# Phase.net
KiCad netlist of a schematic drawn in Altium Designer
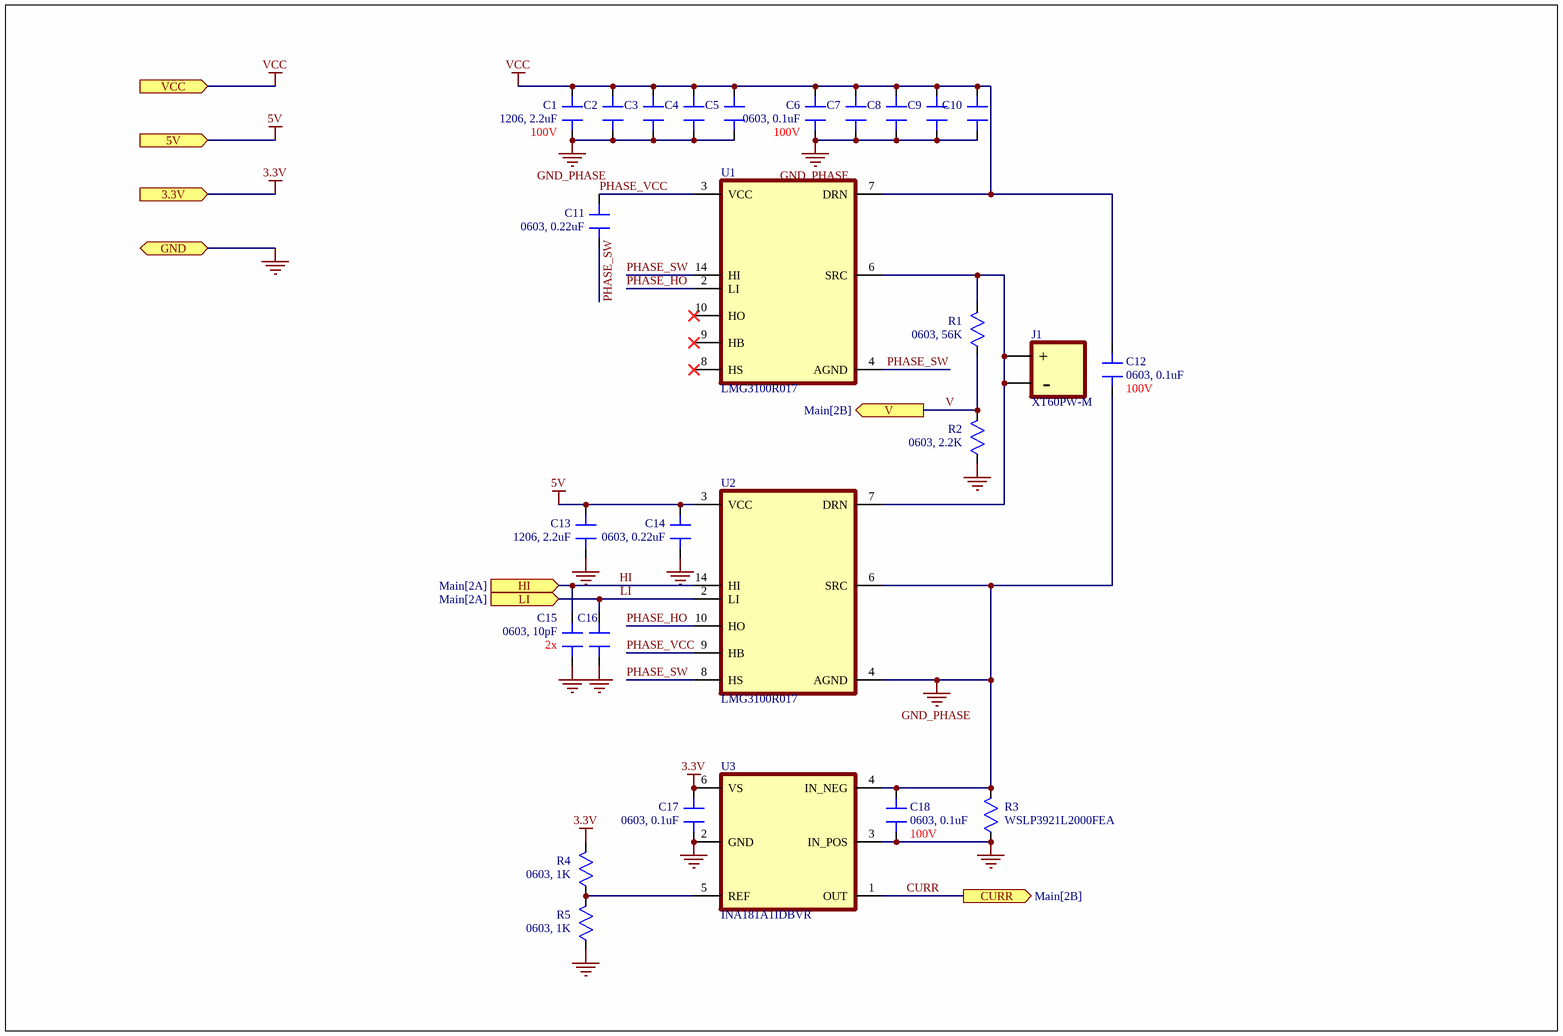
[diagram p0: Phase.SchDoc]

(export (version "E")
  (design (tool "Eeschema 10.0.6"))
  (components
    (comp (ref "C1")
      (value "1206, 2.2uF")
      (footprint "CAP 1206_3216")
      (fields (field (name "VOLTAGE RATING") "100V"))
      (libsource (lib "Passives") (part "1206 Kapasitör"))
    )
    (comp (ref "C2")
      (value "1206, 2.2uF")
      (footprint "CAP 1206_3216")
      (libsource (lib "Passives") (part "1206 Kapasitör"))
    )
    (comp (ref "C3")
      (value "1206, 2.2uF")
      (footprint "CAP 1206_3216")
      (libsource (lib "Passives") (part "1206 Kapasitör"))
    )
    (comp (ref "C4")
      (value "1206, 2.2uF")
      (footprint "CAP 1206_3216")
      (libsource (lib "Passives") (part "1206 Kapasitör"))
    )
    (comp (ref "C5")
      (value "1206, 2.2uF")
      (footprint "CAP 1206_3216")
      (libsource (lib "Passives") (part "1206 Kapasitör"))
    )
    (comp (ref "C6")
      (value "0603, 0.1uF")
      (footprint "CAP 0603_1608")
      (fields (field (name "VOLTAGE RATING") "100V"))
      (libsource (lib "Passives") (part "0603 Kapasitör"))
    )
    (comp (ref "C7")
      (value "0603, 0.1uF")
      (footprint "CAP 0603_1608")
      (libsource (lib "Passives") (part "0603 Kapasitör"))
    )
    (comp (ref "C8")
      (value "0603, 0.1uF")
      (footprint "CAP 0603_1608")
      (libsource (lib "Passives") (part "0603 Kapasitör"))
    )
    (comp (ref "C9")
      (value "0603, 0.1uF")
      (footprint "CAP 0603_1608")
      (libsource (lib "Passives") (part "0603 Kapasitör"))
    )
    (comp (ref "C10")
      (value "0603, 0.1uF")
      (footprint "CAP 0603_1608")
      (libsource (lib "Passives") (part "0603 Kapasitör"))
    )
    (comp (ref "C11")
      (value "0603, 0.22uF")
      (footprint "CAP 0603_1608")
      (libsource (lib "Passives") (part "0603 Kapasitör"))
    )
    (comp (ref "C12")
      (value "0603, 0.1uF")
      (footprint "CAP 0603_1608")
      (fields (field (name "VOLTAGE RATING") "100V"))
      (libsource (lib "Passives") (part "0603 Kapasitör"))
    )
    (comp (ref "C13")
      (value "1206, 2.2uF")
      (footprint "CAP 1206_3216")
      (libsource (lib "Passives") (part "1206 Kapasitör"))
    )
    (comp (ref "C14")
      (value "0603, 0.22uF")
      (footprint "CAP 0603_1608")
      (libsource (lib "Passives") (part "0603 Kapasitör"))
    )
    (comp (ref "C15")
      (value "0603, 10pF")
      (footprint "CAP 0603_1608")
      (libsource (lib "Passives") (part "0603 Kapasitör"))
    )
    (comp (ref "C16")
      (value "0603, 10pF")
      (footprint "CAP 0603_1608")
      (libsource (lib "Passives") (part "0603 Kapasitör"))
    )
    (comp (ref "C17")
      (value "0603, 0.1uF")
      (footprint "CAP 0603_1608")
      (libsource (lib "Passives") (part "0603 Kapasitör"))
    )
    (comp (ref "C18")
      (value "0603, 0.1uF")
      (footprint "CAP 0603_1608")
      (fields (field (name "VOLTAGE RATING") "100V"))
      (libsource (lib "Passives") (part "0603 Kapasitör"))
    )
    (comp (ref "J1") (value "XT60PW-M") (footprint "XT60PW-M") (libsource (lib "XT60PW-M") (part "XT60PW-M")))
    (comp (ref "R1")
      (value "0603, 56K")
      (footprint "RES 0603_1608")
      (libsource (lib "Passives") (part "0603 Direnç"))
    )
    (comp (ref "R2")
      (value "0603, 2.2K")
      (footprint "RES 0603_1608")
      (libsource (lib "Passives") (part "0603 Direnç"))
    )
    (comp (ref "R3")
      (value "WSLP3921L2000FEA")
      (footprint "WSLP3921L2000FEA")
      (libsource (lib "WSLP3921L2000FEA") (part "WSLP3921L2000FEA"))
    )
    (comp (ref "R4")
      (value "0603, 1K")
      (footprint "RES 0603_1608")
      (libsource (lib "Passives") (part "0603 Direnç"))
    )
    (comp (ref "R5")
      (value "0603, 1K")
      (footprint "RES 0603_1608")
      (libsource (lib "Passives") (part "0603 Direnç"))
    )
    (comp (ref "U1")
      (value "LMG3100R017")
      (footprint "LMG3100R017")
      (libsource (lib "LMG3100R017") (part "LMG3100R017"))
    )
    (comp (ref "U2")
      (value "LMG3100R017")
      (footprint "LMG3100R017")
      (libsource (lib "LMG3100R017") (part "LMG3100R017"))
    )
    (comp (ref "U3")
      (value "INA181A1IDBVR")
      (footprint "INA181A1IDBVR")
      (libsource (lib "INA181A1IDBVR") (part "INA181A1IDBVR"))
    )
  )
  (nets
    (net (code "1") (name "/CURR") (class "Default")
      (node (ref "U3") (pin "1") (pinfunction "OUT_1") (pintype "passive"))
    )
    (net (code "2") (name "/HI") (class "Default")
      (node (ref "C15") (pin "2") (pinfunction "2_2") (pintype "passive"))
      (node (ref "U2") (pin "14") (pinfunction "HI_14") (pintype "passive"))
    )
    (net (code "3") (name "/LI") (class "Default")
      (node (ref "C16") (pin "2") (pinfunction "2_2") (pintype "passive"))
      (node (ref "U2") (pin "2") (pinfunction "LI_2") (pintype "passive"))
    )
    (net (code "4") (name "/PHASE_HO") (class "Default")
      (node (ref "U1") (pin "2") (pinfunction "LI_2") (pintype "passive"))
      (node (ref "U2") (pin "10") (pinfunction "HO_10") (pintype "passive"))
    )
    (net (code "5") (name "/PHASE_SW") (class "Default")
      (node (ref "C11") (pin "1") (pinfunction "1_1") (pintype "passive"))
      (node (ref "U1") (pin "14") (pinfunction "HI_14") (pintype "passive"))
      (node (ref "U1") (pin "4") (pinfunction "AGND_4") (pintype "passive"))
      (node (ref "U2") (pin "8") (pinfunction "HS_8") (pintype "passive"))
    )
    (net (code "6") (name "/PHASE_VCC") (class "Default")
      (node (ref "C11") (pin "2") (pinfunction "2_2") (pintype "passive"))
      (node (ref "U1") (pin "3") (pinfunction "VCC_3") (pintype "passive"))
      (node (ref "U2") (pin "9") (pinfunction "HB_9") (pintype "passive"))
    )
    (net (code "7") (name "/V") (class "Default")
      (node (ref "R1") (pin "1") (pinfunction "1_1") (pintype "passive"))
      (node (ref "R2") (pin "2") (pinfunction "2_2") (pintype "passive"))
    )
    (net (code "8") (name "3.3V") (class "Default")
      (node (ref "C17") (pin "2") (pinfunction "2_2") (pintype "passive"))
      (node (ref "R4") (pin "2") (pinfunction "2_2") (pintype "passive"))
      (node (ref "U3") (pin "6") (pinfunction "VS_6") (pintype "passive"))
    )
    (net (code "9") (name "5V") (class "Default")
      (node (ref "C13") (pin "2") (pinfunction "2_2") (pintype "passive"))
      (node (ref "C14") (pin "2") (pinfunction "2_2") (pintype "passive"))
      (node (ref "U2") (pin "3") (pinfunction "VCC_3") (pintype "passive"))
    )
    (net (code "10") (name "GND") (class "Default")
      (node (ref "C13") (pin "1") (pinfunction "1_1") (pintype "passive"))
      (node (ref "C14") (pin "1") (pinfunction "1_1") (pintype "passive"))
      (node (ref "C15") (pin "1") (pinfunction "1_1") (pintype "passive"))
      (node (ref "C16") (pin "1") (pinfunction "1_1") (pintype "passive"))
      (node (ref "C17") (pin "1") (pinfunction "1_1") (pintype "passive"))
      (node (ref "C18") (pin "1") (pinfunction "1_1") (pintype "passive"))
      (node (ref "R2") (pin "1") (pinfunction "1_1") (pintype "passive"))
      (node (ref "R3") (pin "1") (pinfunction "1_1") (pintype "passive"))
      (node (ref "R5") (pin "1") (pinfunction "1_1") (pintype "passive"))
      (node (ref "U3") (pin "2") (pinfunction "GND_2") (pintype "passive"))
      (node (ref "U3") (pin "3") (pinfunction "IN_POS_3") (pintype "passive"))
    )
    (net (code "11") (name "GND_PHASE") (class "Default")
      (node (ref "C1") (pin "1") (pinfunction "1_1") (pintype "passive"))
      (node (ref "C10") (pin "1") (pinfunction "1_1") (pintype "passive"))
      (node (ref "C12") (pin "1") (pinfunction "1_1") (pintype "passive"))
      (node (ref "C18") (pin "2") (pinfunction "2_2") (pintype "passive"))
      (node (ref "C2") (pin "1") (pinfunction "1_1") (pintype "passive"))
      (node (ref "C3") (pin "1") (pinfunction "1_1") (pintype "passive"))
      (node (ref "C4") (pin "1") (pinfunction "1_1") (pintype "passive"))
      (node (ref "C5") (pin "1") (pinfunction "1_1") (pintype "passive"))
      (node (ref "C6") (pin "1") (pinfunction "1_1") (pintype "passive"))
      (node (ref "C7") (pin "1") (pinfunction "1_1") (pintype "passive"))
      (node (ref "C8") (pin "1") (pinfunction "1_1") (pintype "passive"))
      (node (ref "C9") (pin "1") (pinfunction "1_1") (pintype "passive"))
      (node (ref "R3") (pin "2") (pinfunction "2_2") (pintype "passive"))
      (node (ref "U2") (pin "4") (pinfunction "AGND_4") (pintype "passive"))
      (node (ref "U2") (pin "6") (pinfunction "SRC_6") (pintype "passive"))
      (node (ref "U3") (pin "4") (pinfunction "IN_NEG_4") (pintype "passive"))
    )
    (net (code "12") (name "Net-(J1-+)") (class "Default")
      (node (ref "J1") (pin "1") (pinfunction "+_1") (pintype "passive"))
      (node (ref "J1") (pin "2") (pinfunction "-_2") (pintype "passive"))
      (node (ref "R1") (pin "2") (pinfunction "2_2") (pintype "passive"))
      (node (ref "U1") (pin "6") (pinfunction "SRC_6") (pintype "passive"))
      (node (ref "U2") (pin "7") (pinfunction "DRN_7") (pintype "passive"))
    )
    (net (code "13") (name "Net-(U3-REF)") (class "Default")
      (node (ref "R4") (pin "1") (pinfunction "1_1") (pintype "passive"))
      (node (ref "R5") (pin "2") (pinfunction "2_2") (pintype "passive"))
      (node (ref "U3") (pin "5") (pinfunction "REF_5") (pintype "passive"))
    )
    (net (code "14") (name "VCC") (class "Default")
      (node (ref "C1") (pin "2") (pinfunction "2_2") (pintype "passive"))
      (node (ref "C10") (pin "2") (pinfunction "2_2") (pintype "passive"))
      (node (ref "C12") (pin "2") (pinfunction "2_2") (pintype "passive"))
      (node (ref "C2") (pin "2") (pinfunction "2_2") (pintype "passive"))
      (node (ref "C3") (pin "2") (pinfunction "2_2") (pintype "passive"))
      (node (ref "C4") (pin "2") (pinfunction "2_2") (pintype "passive"))
      (node (ref "C5") (pin "2") (pinfunction "2_2") (pintype "passive"))
      (node (ref "C6") (pin "2") (pinfunction "2_2") (pintype "passive"))
      (node (ref "C7") (pin "2") (pinfunction "2_2") (pintype "passive"))
      (node (ref "C8") (pin "2") (pinfunction "2_2") (pintype "passive"))
      (node (ref "C9") (pin "2") (pinfunction "2_2") (pintype "passive"))
      (node (ref "U1") (pin "7") (pinfunction "DRN_7") (pintype "passive"))
    )
    (net (code "15") (name "unconnected-(U1-HB-Pad9)") (class "Default")
      (node (ref "U1") (pin "9") (pinfunction "HB_9") (pintype "passive+no_connect"))
    )
    (net (code "16") (name "unconnected-(U1-HO-Pad10)") (class "Default")
      (node (ref "U1") (pin "10") (pinfunction "HO_10") (pintype "passive+no_connect"))
    )
    (net (code "17") (name "unconnected-(U1-HS-Pad8)") (class "Default")
      (node (ref "U1") (pin "8") (pinfunction "HS_8") (pintype "passive+no_connect"))
    )
  )
)
